# SparkFun_Photon_Wearable_Shield.net
KiCad netlist of a schematic drawn in EAGLE
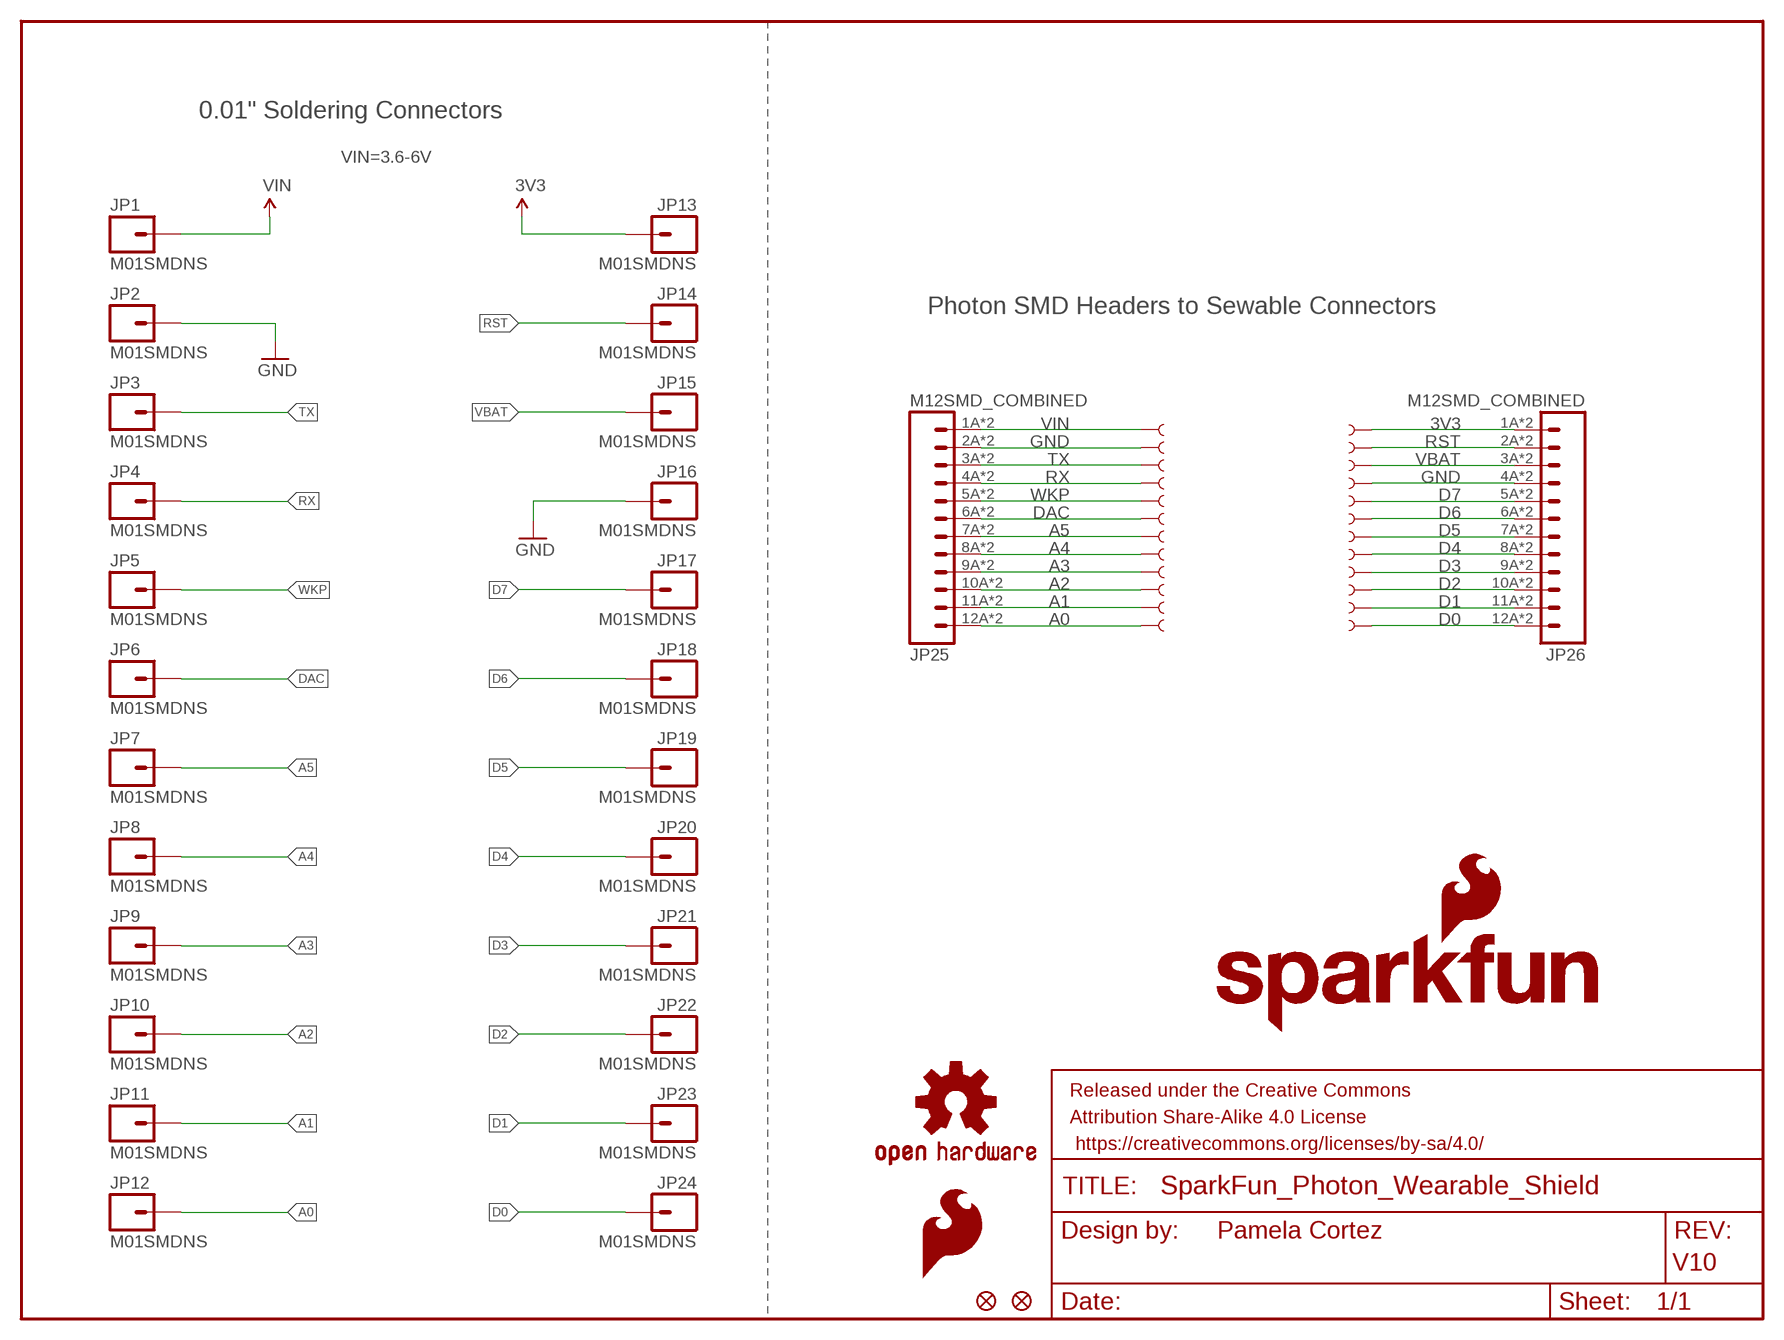
[diagram p0: schematic, sheet 1]

(export (version "E")
  (design (tool "Eeschema 10.0.6"))
  (components
    (comp (ref "FID1")
      (value "FIDUCIAL1X2")
      (footprint "eagle-import:FIDUCIAL-1X2")
      (libsource (lib "eagle-import") (part "FIDUCIAL1X2"))
    )
    (comp (ref "FID2")
      (value "FIDUCIAL1X2")
      (footprint "eagle-import:FIDUCIAL-1X2")
      (libsource (lib "eagle-import") (part "FIDUCIAL1X2"))
    )
    (comp (ref "FRAME1")
      (value "FRAME-LETTER")
      (footprint "eagle-import:CREATIVE_COMMONS")
      (fields (field (name "DESIGNER") "NAME"))
      (libsource (lib "eagle-import") (part "FRAME-LETTER"))
    )
    (comp (ref "J1")
      (value "PAD")
      (footprint "eagle-import:PAD-LONG-2-SIDED")
      (libsource (lib "eagle-import") (part "PAD"))
    )
    (comp (ref "J2")
      (value "PAD")
      (footprint "eagle-import:PAD-LONG-2-SIDED")
      (libsource (lib "eagle-import") (part "PAD"))
    )
    (comp (ref "J3")
      (value "PAD")
      (footprint "eagle-import:PAD-LONG-2-SIDED")
      (libsource (lib "eagle-import") (part "PAD"))
    )
    (comp (ref "J4")
      (value "PAD")
      (footprint "eagle-import:PAD-LONG-2-SIDED")
      (libsource (lib "eagle-import") (part "PAD"))
    )
    (comp (ref "J5")
      (value "PAD")
      (footprint "eagle-import:PAD-LONG-2-SIDED")
      (libsource (lib "eagle-import") (part "PAD"))
    )
    (comp (ref "J6")
      (value "PAD")
      (footprint "eagle-import:PAD-LONG-2-SIDED")
      (libsource (lib "eagle-import") (part "PAD"))
    )
    (comp (ref "J7")
      (value "PAD")
      (footprint "eagle-import:PAD-LONG-2-SIDED")
      (libsource (lib "eagle-import") (part "PAD"))
    )
    (comp (ref "J8")
      (value "PAD")
      (footprint "eagle-import:PAD-LONG-2-SIDED")
      (libsource (lib "eagle-import") (part "PAD"))
    )
    (comp (ref "J9")
      (value "PAD")
      (footprint "eagle-import:PAD-LONG-2-SIDED")
      (libsource (lib "eagle-import") (part "PAD"))
    )
    (comp (ref "J10")
      (value "PAD")
      (footprint "eagle-import:PAD-LONG-2-SIDED")
      (libsource (lib "eagle-import") (part "PAD"))
    )
    (comp (ref "J11")
      (value "PAD")
      (footprint "eagle-import:PAD-LONG-2-SIDED")
      (libsource (lib "eagle-import") (part "PAD"))
    )
    (comp (ref "J12")
      (value "PAD")
      (footprint "eagle-import:PAD-LONG-2-SIDED")
      (libsource (lib "eagle-import") (part "PAD"))
    )
    (comp (ref "J13")
      (value "PAD")
      (footprint "eagle-import:PAD-LONG-2-SIDED")
      (libsource (lib "eagle-import") (part "PAD"))
    )
    (comp (ref "J14")
      (value "PAD")
      (footprint "eagle-import:PAD-LONG-2-SIDED")
      (libsource (lib "eagle-import") (part "PAD"))
    )
    (comp (ref "J15")
      (value "PAD")
      (footprint "eagle-import:PAD-LONG-2-SIDED")
      (libsource (lib "eagle-import") (part "PAD"))
    )
    (comp (ref "J16")
      (value "PAD")
      (footprint "eagle-import:PAD-LONG-2-SIDED")
      (libsource (lib "eagle-import") (part "PAD"))
    )
    (comp (ref "J17")
      (value "PAD")
      (footprint "eagle-import:PAD-LONG-2-SIDED")
      (libsource (lib "eagle-import") (part "PAD"))
    )
    (comp (ref "J18")
      (value "PAD")
      (footprint "eagle-import:PAD-LONG-2-SIDED")
      (libsource (lib "eagle-import") (part "PAD"))
    )
    (comp (ref "J19")
      (value "PAD")
      (footprint "eagle-import:PAD-LONG-2-SIDED")
      (libsource (lib "eagle-import") (part "PAD"))
    )
    (comp (ref "J20")
      (value "PAD")
      (footprint "eagle-import:PAD-LONG-2-SIDED")
      (libsource (lib "eagle-import") (part "PAD"))
    )
    (comp (ref "J21")
      (value "PAD")
      (footprint "eagle-import:PAD-LONG-2-SIDED")
      (libsource (lib "eagle-import") (part "PAD"))
    )
    (comp (ref "J22")
      (value "PAD")
      (footprint "eagle-import:PAD-LONG-2-SIDED")
      (libsource (lib "eagle-import") (part "PAD"))
    )
    (comp (ref "J23")
      (value "PAD")
      (footprint "eagle-import:PAD-LONG-2-SIDED")
      (libsource (lib "eagle-import") (part "PAD"))
    )
    (comp (ref "J24")
      (value "PAD")
      (footprint "eagle-import:PAD-LONG-2-SIDED")
      (libsource (lib "eagle-import") (part "PAD"))
    )
    (comp (ref "JP1")
      (value "M01SMDNS")
      (footprint "eagle-import:1X01NS")
      (libsource (lib "eagle-import") (part "M01SMDNS"))
    )
    (comp (ref "JP2")
      (value "M01SMDNS")
      (footprint "eagle-import:1X01NS")
      (libsource (lib "eagle-import") (part "M01SMDNS"))
    )
    (comp (ref "JP3")
      (value "M01SMDNS")
      (footprint "eagle-import:1X01NS")
      (libsource (lib "eagle-import") (part "M01SMDNS"))
    )
    (comp (ref "JP4")
      (value "M01SMDNS")
      (footprint "eagle-import:1X01NS")
      (libsource (lib "eagle-import") (part "M01SMDNS"))
    )
    (comp (ref "JP5")
      (value "M01SMDNS")
      (footprint "eagle-import:1X01NS")
      (libsource (lib "eagle-import") (part "M01SMDNS"))
    )
    (comp (ref "JP6")
      (value "M01SMDNS")
      (footprint "eagle-import:1X01NS")
      (libsource (lib "eagle-import") (part "M01SMDNS"))
    )
    (comp (ref "JP7")
      (value "M01SMDNS")
      (footprint "eagle-import:1X01NS")
      (libsource (lib "eagle-import") (part "M01SMDNS"))
    )
    (comp (ref "JP8")
      (value "M01SMDNS")
      (footprint "eagle-import:1X01NS")
      (libsource (lib "eagle-import") (part "M01SMDNS"))
    )
    (comp (ref "JP9")
      (value "M01SMDNS")
      (footprint "eagle-import:1X01NS")
      (libsource (lib "eagle-import") (part "M01SMDNS"))
    )
    (comp (ref "JP10")
      (value "M01SMDNS")
      (footprint "eagle-import:1X01NS")
      (libsource (lib "eagle-import") (part "M01SMDNS"))
    )
    (comp (ref "JP11")
      (value "M01SMDNS")
      (footprint "eagle-import:1X01NS")
      (libsource (lib "eagle-import") (part "M01SMDNS"))
    )
    (comp (ref "JP12")
      (value "M01SMDNS")
      (footprint "eagle-import:1X01NS")
      (libsource (lib "eagle-import") (part "M01SMDNS"))
    )
    (comp (ref "JP13")
      (value "M01SMDNS")
      (footprint "eagle-import:1X01NS")
      (libsource (lib "eagle-import") (part "M01SMDNS"))
    )
    (comp (ref "JP14")
      (value "M01SMDNS")
      (footprint "eagle-import:1X01NS")
      (libsource (lib "eagle-import") (part "M01SMDNS"))
    )
    (comp (ref "JP15")
      (value "M01SMDNS")
      (footprint "eagle-import:1X01NS")
      (libsource (lib "eagle-import") (part "M01SMDNS"))
    )
    (comp (ref "JP16")
      (value "M01SMDNS")
      (footprint "eagle-import:1X01NS")
      (libsource (lib "eagle-import") (part "M01SMDNS"))
    )
    (comp (ref "JP17")
      (value "M01SMDNS")
      (footprint "eagle-import:1X01NS")
      (libsource (lib "eagle-import") (part "M01SMDNS"))
    )
    (comp (ref "JP18")
      (value "M01SMDNS")
      (footprint "eagle-import:1X01NS")
      (libsource (lib "eagle-import") (part "M01SMDNS"))
    )
    (comp (ref "JP19")
      (value "M01SMDNS")
      (footprint "eagle-import:1X01NS")
      (libsource (lib "eagle-import") (part "M01SMDNS"))
    )
    (comp (ref "JP20")
      (value "M01SMDNS")
      (footprint "eagle-import:1X01NS")
      (libsource (lib "eagle-import") (part "M01SMDNS"))
    )
    (comp (ref "JP21")
      (value "M01SMDNS")
      (footprint "eagle-import:1X01NS")
      (libsource (lib "eagle-import") (part "M01SMDNS"))
    )
    (comp (ref "JP22")
      (value "M01SMDNS")
      (footprint "eagle-import:1X01NS")
      (libsource (lib "eagle-import") (part "M01SMDNS"))
    )
    (comp (ref "JP23")
      (value "M01SMDNS")
      (footprint "eagle-import:1X01NS")
      (libsource (lib "eagle-import") (part "M01SMDNS"))
    )
    (comp (ref "JP24")
      (value "M01SMDNS")
      (footprint "eagle-import:1X01NS")
      (libsource (lib "eagle-import") (part "M01SMDNS"))
    )
    (comp (ref "JP25")
      (value "M12SMD_COMBINED")
      (footprint "eagle-import:1X12_SMD_COMBINED")
      (libsource (lib "eagle-import") (part "M12SMD_COMBINED"))
    )
    (comp (ref "JP26")
      (value "M12SMD_COMBINED")
      (footprint "eagle-import:1X12_SMD_COMBINED")
      (libsource (lib "eagle-import") (part "M12SMD_COMBINED"))
    )
    (comp (ref "LOGO1")
      (value "SFE_LOGO_FLAME.2_INCH")
      (footprint "eagle-import:SFE_LOGO_FLAME_.2")
      (libsource (lib "eagle-import") (part "SFE_LOGO_FLAME.2_INCH"))
    )
    (comp (ref "LOGO2")
      (value "OSHW-LOGOM")
      (footprint "eagle-import:OSHW-LOGO-M")
      (libsource (lib "eagle-import") (part "OSHW-LOGOM"))
    )
    (comp (ref "LOGO3")
      (value "SFE_LOGO_NAME_FLAME.1_INCH")
      (footprint "eagle-import:SFE_LOGO_NAME_FLAME_.1")
      (libsource (lib "eagle-import") (part "SFE_LOGO_NAME_FLAME.1_INCH"))
    )
  )
  (nets
    (net (code "1") (name "3V3") (class "Default")
      (node (ref "J13") (pin "1") (pinfunction "1_1") (pintype "bidirectional"))
      (node (ref "JP13") (pin "1") (pinfunction "1_1") (pintype "passive"))
      (node (ref "JP26") (pin "1A") (pinfunction "1_1A") (pintype "passive"))
      (node (ref "JP26") (pin "1B") (pinfunction "1_1B") (pintype "passive"))
    )
    (net (code "2") (name "A0") (class "Default")
      (node (ref "J12") (pin "1") (pinfunction "1_1") (pintype "bidirectional"))
      (node (ref "JP12") (pin "1") (pinfunction "1_1") (pintype "passive"))
      (node (ref "JP25") (pin "12A") (pinfunction "12_12A") (pintype "passive"))
      (node (ref "JP25") (pin "12B") (pinfunction "12_12B") (pintype "passive"))
    )
    (net (code "3") (name "A1") (class "Default")
      (node (ref "J11") (pin "1") (pinfunction "1_1") (pintype "bidirectional"))
      (node (ref "JP11") (pin "1") (pinfunction "1_1") (pintype "passive"))
      (node (ref "JP25") (pin "11A") (pinfunction "11_11A") (pintype "passive"))
      (node (ref "JP25") (pin "11B") (pinfunction "11_11B") (pintype "passive"))
    )
    (net (code "4") (name "A2") (class "Default")
      (node (ref "J10") (pin "1") (pinfunction "1_1") (pintype "bidirectional"))
      (node (ref "JP10") (pin "1") (pinfunction "1_1") (pintype "passive"))
      (node (ref "JP25") (pin "10A") (pinfunction "10_10A") (pintype "passive"))
      (node (ref "JP25") (pin "10B") (pinfunction "10_10B") (pintype "passive"))
    )
    (net (code "5") (name "A3") (class "Default")
      (node (ref "J9") (pin "1") (pinfunction "1_1") (pintype "bidirectional"))
      (node (ref "JP25") (pin "9A") (pinfunction "9_9A") (pintype "passive"))
      (node (ref "JP25") (pin "9B") (pinfunction "9_9B") (pintype "passive"))
      (node (ref "JP9") (pin "1") (pinfunction "1_1") (pintype "passive"))
    )
    (net (code "6") (name "A4") (class "Default")
      (node (ref "J8") (pin "1") (pinfunction "1_1") (pintype "bidirectional"))
      (node (ref "JP25") (pin "8A") (pinfunction "8_8A") (pintype "passive"))
      (node (ref "JP25") (pin "8B") (pinfunction "8_8B") (pintype "passive"))
      (node (ref "JP8") (pin "1") (pinfunction "1_1") (pintype "passive"))
    )
    (net (code "7") (name "A5") (class "Default")
      (node (ref "J7") (pin "1") (pinfunction "1_1") (pintype "bidirectional"))
      (node (ref "JP25") (pin "7A") (pinfunction "7_7A") (pintype "passive"))
      (node (ref "JP25") (pin "7B") (pinfunction "7_7B") (pintype "passive"))
      (node (ref "JP7") (pin "1") (pinfunction "1_1") (pintype "passive"))
    )
    (net (code "8") (name "D0") (class "Default")
      (node (ref "J24") (pin "1") (pinfunction "1_1") (pintype "bidirectional"))
      (node (ref "JP24") (pin "1") (pinfunction "1_1") (pintype "passive"))
      (node (ref "JP26") (pin "12A") (pinfunction "12_12A") (pintype "passive"))
      (node (ref "JP26") (pin "12B") (pinfunction "12_12B") (pintype "passive"))
    )
    (net (code "9") (name "D1") (class "Default")
      (node (ref "J23") (pin "1") (pinfunction "1_1") (pintype "bidirectional"))
      (node (ref "JP23") (pin "1") (pinfunction "1_1") (pintype "passive"))
      (node (ref "JP26") (pin "11A") (pinfunction "11_11A") (pintype "passive"))
      (node (ref "JP26") (pin "11B") (pinfunction "11_11B") (pintype "passive"))
    )
    (net (code "10") (name "D2") (class "Default")
      (node (ref "J22") (pin "1") (pinfunction "1_1") (pintype "bidirectional"))
      (node (ref "JP22") (pin "1") (pinfunction "1_1") (pintype "passive"))
      (node (ref "JP26") (pin "10A") (pinfunction "10_10A") (pintype "passive"))
      (node (ref "JP26") (pin "10B") (pinfunction "10_10B") (pintype "passive"))
    )
    (net (code "11") (name "D3") (class "Default")
      (node (ref "J21") (pin "1") (pinfunction "1_1") (pintype "bidirectional"))
      (node (ref "JP21") (pin "1") (pinfunction "1_1") (pintype "passive"))
      (node (ref "JP26") (pin "9A") (pinfunction "9_9A") (pintype "passive"))
      (node (ref "JP26") (pin "9B") (pinfunction "9_9B") (pintype "passive"))
    )
    (net (code "12") (name "D4") (class "Default")
      (node (ref "J20") (pin "1") (pinfunction "1_1") (pintype "bidirectional"))
      (node (ref "JP20") (pin "1") (pinfunction "1_1") (pintype "passive"))
      (node (ref "JP26") (pin "8A") (pinfunction "8_8A") (pintype "passive"))
      (node (ref "JP26") (pin "8B") (pinfunction "8_8B") (pintype "passive"))
    )
    (net (code "13") (name "D5") (class "Default")
      (node (ref "J19") (pin "1") (pinfunction "1_1") (pintype "bidirectional"))
      (node (ref "JP19") (pin "1") (pinfunction "1_1") (pintype "passive"))
      (node (ref "JP26") (pin "7A") (pinfunction "7_7A") (pintype "passive"))
      (node (ref "JP26") (pin "7B") (pinfunction "7_7B") (pintype "passive"))
    )
    (net (code "14") (name "D6") (class "Default")
      (node (ref "J18") (pin "1") (pinfunction "1_1") (pintype "bidirectional"))
      (node (ref "JP18") (pin "1") (pinfunction "1_1") (pintype "passive"))
      (node (ref "JP26") (pin "6A") (pinfunction "6_6A") (pintype "passive"))
      (node (ref "JP26") (pin "6B") (pinfunction "6_6B") (pintype "passive"))
    )
    (net (code "15") (name "D7") (class "Default")
      (node (ref "J17") (pin "1") (pinfunction "1_1") (pintype "bidirectional"))
      (node (ref "JP17") (pin "1") (pinfunction "1_1") (pintype "passive"))
      (node (ref "JP26") (pin "5A") (pinfunction "5_5A") (pintype "passive"))
      (node (ref "JP26") (pin "5B") (pinfunction "5_5B") (pintype "passive"))
    )
    (net (code "16") (name "DAC") (class "Default")
      (node (ref "J6") (pin "1") (pinfunction "1_1") (pintype "bidirectional"))
      (node (ref "JP25") (pin "6A") (pinfunction "6_6A") (pintype "passive"))
      (node (ref "JP25") (pin "6B") (pinfunction "6_6B") (pintype "passive"))
      (node (ref "JP6") (pin "1") (pinfunction "1_1") (pintype "passive"))
    )
    (net (code "17") (name "GND") (class "Default")
      (node (ref "J16") (pin "1") (pinfunction "1_1") (pintype "bidirectional"))
      (node (ref "J2") (pin "1") (pinfunction "1_1") (pintype "bidirectional"))
      (node (ref "JP16") (pin "1") (pinfunction "1_1") (pintype "passive"))
      (node (ref "JP2") (pin "1") (pinfunction "1_1") (pintype "passive"))
      (node (ref "JP25") (pin "2A") (pinfunction "2_2A") (pintype "passive"))
      (node (ref "JP25") (pin "2B") (pinfunction "2_2B") (pintype "passive"))
      (node (ref "JP26") (pin "4A") (pinfunction "4_4A") (pintype "passive"))
      (node (ref "JP26") (pin "4B") (pinfunction "4_4B") (pintype "passive"))
    )
    (net (code "18") (name "RST") (class "Default")
      (node (ref "J14") (pin "1") (pinfunction "1_1") (pintype "bidirectional"))
      (node (ref "JP14") (pin "1") (pinfunction "1_1") (pintype "passive"))
      (node (ref "JP26") (pin "2A") (pinfunction "2_2A") (pintype "passive"))
      (node (ref "JP26") (pin "2B") (pinfunction "2_2B") (pintype "passive"))
    )
    (net (code "19") (name "RX") (class "Default")
      (node (ref "J4") (pin "1") (pinfunction "1_1") (pintype "bidirectional"))
      (node (ref "JP25") (pin "4A") (pinfunction "4_4A") (pintype "passive"))
      (node (ref "JP25") (pin "4B") (pinfunction "4_4B") (pintype "passive"))
      (node (ref "JP4") (pin "1") (pinfunction "1_1") (pintype "passive"))
    )
    (net (code "20") (name "TX") (class "Default")
      (node (ref "J3") (pin "1") (pinfunction "1_1") (pintype "bidirectional"))
      (node (ref "JP25") (pin "3A") (pinfunction "3_3A") (pintype "passive"))
      (node (ref "JP25") (pin "3B") (pinfunction "3_3B") (pintype "passive"))
      (node (ref "JP3") (pin "1") (pinfunction "1_1") (pintype "passive"))
    )
    (net (code "21") (name "VBAT") (class "Default")
      (node (ref "J15") (pin "1") (pinfunction "1_1") (pintype "bidirectional"))
      (node (ref "JP15") (pin "1") (pinfunction "1_1") (pintype "passive"))
      (node (ref "JP26") (pin "3A") (pinfunction "3_3A") (pintype "passive"))
      (node (ref "JP26") (pin "3B") (pinfunction "3_3B") (pintype "passive"))
    )
    (net (code "22") (name "VIN") (class "Default")
      (node (ref "J1") (pin "1") (pinfunction "1_1") (pintype "bidirectional"))
      (node (ref "JP1") (pin "1") (pinfunction "1_1") (pintype "passive"))
      (node (ref "JP25") (pin "1A") (pinfunction "1_1A") (pintype "passive"))
      (node (ref "JP25") (pin "1B") (pinfunction "1_1B") (pintype "passive"))
    )
    (net (code "23") (name "WKP") (class "Default")
      (node (ref "J5") (pin "1") (pinfunction "1_1") (pintype "bidirectional"))
      (node (ref "JP25") (pin "5A") (pinfunction "5_5A") (pintype "passive"))
      (node (ref "JP25") (pin "5B") (pinfunction "5_5B") (pintype "passive"))
      (node (ref "JP5") (pin "1") (pinfunction "1_1") (pintype "passive"))
    )
  )
)
